# BSPD_Breakout_manufactured_2016-11-07.net
KiCad netlist of a schematic drawn in EAGLE
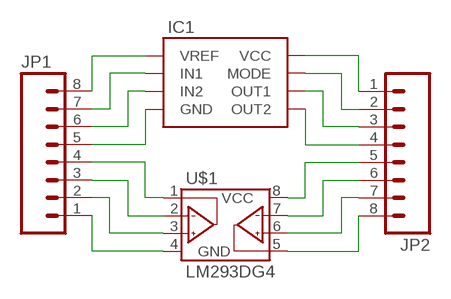
[diagram p0: schematic, sheet 1]

(export (version "E")
  (design (tool "Eeschema 10.0.6"))
  (components
    (comp (ref "IC1")
      (value "MC34161DG")
      (footprint "eagle-import:SOIC-08")
      (libsource (lib "eagle-import") (part "MC34161DG"))
    )
    (comp (ref "JP1")
      (value "M08")
      (footprint "eagle-import:1X08")
      (libsource (lib "eagle-import") (part "M08"))
    )
    (comp (ref "JP2")
      (value "M08")
      (footprint "eagle-import:1X08")
      (libsource (lib "eagle-import") (part "M08"))
    )
    (comp (ref "U$1")
      (value "LM293DG4")
      (footprint "eagle-import:SOIC-08")
      (libsource (lib "eagle-import") (part "LM293DG4"))
    )
  )
  (nets
    (net (code "1") (name "Net-(IC1-GND)") (class "Default")
      (node (ref "IC1") (pin "4") (pinfunction "GND_4") (pintype "passive"))
      (node (ref "JP1") (pin "5") (pinfunction "5_5") (pintype "passive"))
    )
    (net (code "2") (name "Net-(IC1-IN1)") (class "Default")
      (node (ref "IC1") (pin "2") (pinfunction "IN1_2") (pintype "passive"))
      (node (ref "JP1") (pin "7") (pinfunction "7_7") (pintype "passive"))
    )
    (net (code "3") (name "Net-(IC1-IN2)") (class "Default")
      (node (ref "IC1") (pin "3") (pinfunction "IN2_3") (pintype "passive"))
      (node (ref "JP1") (pin "6") (pinfunction "6_6") (pintype "passive"))
    )
    (net (code "4") (name "Net-(IC1-MODE)") (class "Default")
      (node (ref "IC1") (pin "7") (pinfunction "MODE_7") (pintype "passive"))
      (node (ref "JP2") (pin "2") (pinfunction "2_2") (pintype "passive"))
    )
    (net (code "5") (name "Net-(IC1-OUT1)") (class "Default")
      (node (ref "IC1") (pin "6") (pinfunction "OUT1_6") (pintype "passive"))
      (node (ref "JP2") (pin "3") (pinfunction "3_3") (pintype "passive"))
    )
    (net (code "6") (name "Net-(IC1-OUT2)") (class "Default")
      (node (ref "IC1") (pin "5") (pinfunction "OUT2_5") (pintype "passive"))
      (node (ref "JP2") (pin "4") (pinfunction "4_4") (pintype "passive"))
    )
    (net (code "7") (name "Net-(IC1-VCC)") (class "Default")
      (node (ref "IC1") (pin "8") (pinfunction "VCC_8") (pintype "passive"))
      (node (ref "JP2") (pin "1") (pinfunction "1_1") (pintype "passive"))
    )
    (net (code "8") (name "Net-(IC1-VREF)") (class "Default")
      (node (ref "IC1") (pin "1") (pinfunction "VREF_1") (pintype "passive"))
      (node (ref "JP1") (pin "8") (pinfunction "8_8") (pintype "passive"))
    )
    (net (code "9") (name "Net-(U$1-1IN+)") (class "Default")
      (node (ref "JP1") (pin "2") (pinfunction "2_2") (pintype "passive"))
      (node (ref "U$1") (pin "3") (pinfunction "1IN+_3") (pintype "passive"))
    )
    (net (code "10") (name "Net-(U$1-1IN-)") (class "Default")
      (node (ref "JP1") (pin "3") (pinfunction "3_3") (pintype "passive"))
      (node (ref "U$1") (pin "2") (pinfunction "1IN-_2") (pintype "passive"))
    )
    (net (code "11") (name "Net-(U$1-1OUT)") (class "Default")
      (node (ref "JP1") (pin "4") (pinfunction "4_4") (pintype "passive"))
      (node (ref "U$1") (pin "1") (pinfunction "1OUT_1") (pintype "passive"))
    )
    (net (code "12") (name "Net-(U$1-2IN+)") (class "Default")
      (node (ref "JP2") (pin "8") (pinfunction "8_8") (pintype "passive"))
      (node (ref "U$1") (pin "5") (pinfunction "2IN+_5") (pintype "passive"))
    )
    (net (code "13") (name "Net-(U$1-2IN-)") (class "Default")
      (node (ref "JP2") (pin "7") (pinfunction "7_7") (pintype "passive"))
      (node (ref "U$1") (pin "6") (pinfunction "2IN-_6") (pintype "passive"))
    )
    (net (code "14") (name "Net-(U$1-2OUT)") (class "Default")
      (node (ref "JP2") (pin "6") (pinfunction "6_6") (pintype "passive"))
      (node (ref "U$1") (pin "7") (pinfunction "2OUT_7") (pintype "passive"))
    )
    (net (code "15") (name "Net-(U$1-GND)") (class "Default")
      (node (ref "JP1") (pin "1") (pinfunction "1_1") (pintype "passive"))
      (node (ref "U$1") (pin "4") (pinfunction "GND_4") (pintype "passive"))
    )
    (net (code "16") (name "Net-(U$1-VCC)") (class "Default")
      (node (ref "JP2") (pin "5") (pinfunction "5_5") (pintype "passive"))
      (node (ref "U$1") (pin "8") (pinfunction "VCC_8") (pintype "passive"))
    )
  )
)
